# vlsibreakout.net
KiCad netlist of a schematic drawn in EAGLE
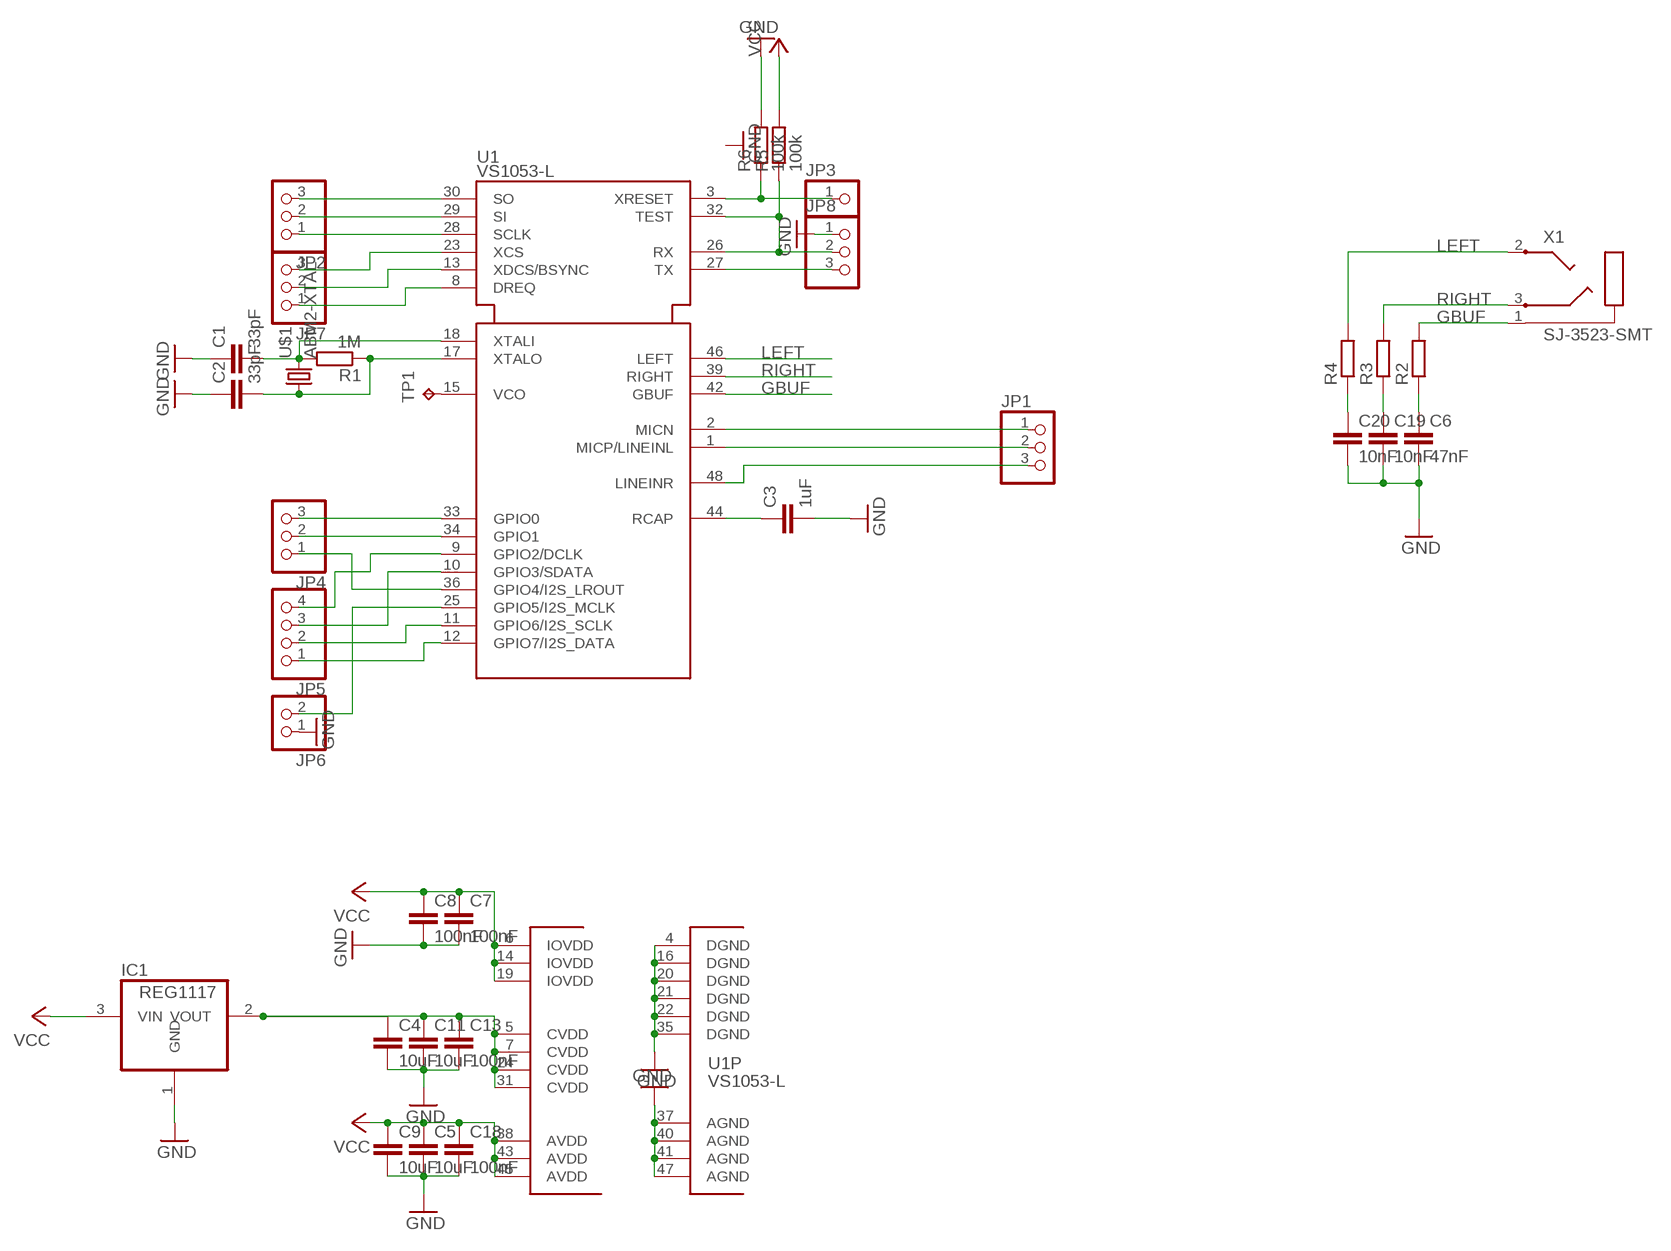
[diagram p0: schematic, sheet 1]

(export (version "E")
  (design (tool "Eeschema 10.0.6"))
  (components
    (comp (ref "C1")
      (value "33pF")
      (footprint "eagle-import:C0805")
      (libsource (lib "eagle-import") (part "C-EUC0805"))
    )
    (comp (ref "C2")
      (value "33pF")
      (footprint "eagle-import:C0805")
      (libsource (lib "eagle-import") (part "C-EUC0805"))
    )
    (comp (ref "C3")
      (value "1uF")
      (footprint "eagle-import:C0805")
      (libsource (lib "eagle-import") (part "C-EUC0805"))
    )
    (comp (ref "C4")
      (value "10uF")
      (footprint "eagle-import:C0805")
      (libsource (lib "eagle-import") (part "resistor_C-EUC0805"))
    )
    (comp (ref "C5")
      (value "10uF")
      (footprint "eagle-import:C0805")
      (libsource (lib "eagle-import") (part "resistor_C-EUC0805"))
    )
    (comp (ref "C6")
      (value "47nF")
      (footprint "eagle-import:C0603")
      (libsource (lib "eagle-import") (part "C-EUC0603"))
    )
    (comp (ref "C7")
      (value "100nF")
      (footprint "eagle-import:C0805")
      (libsource (lib "eagle-import") (part "resistor_C-EUC0805"))
    )
    (comp (ref "C8")
      (value "100nF")
      (footprint "eagle-import:C0805")
      (libsource (lib "eagle-import") (part "resistor_C-EUC0805"))
    )
    (comp (ref "C9")
      (value "10uF")
      (footprint "eagle-import:C0805")
      (libsource (lib "eagle-import") (part "resistor_C-EUC0805"))
    )
    (comp (ref "C11")
      (value "10uF")
      (footprint "eagle-import:C0805")
      (libsource (lib "eagle-import") (part "resistor_C-EUC0805"))
    )
    (comp (ref "C13")
      (value "100nF")
      (footprint "eagle-import:C0805")
      (libsource (lib "eagle-import") (part "resistor_C-EUC0805"))
    )
    (comp (ref "C18")
      (value "100nF")
      (footprint "eagle-import:C0805")
      (libsource (lib "eagle-import") (part "resistor_C-EUC0805"))
    )
    (comp (ref "C19")
      (value "10nF")
      (footprint "eagle-import:C0603")
      (libsource (lib "eagle-import") (part "C-EUC0603"))
    )
    (comp (ref "C20")
      (value "10nF")
      (footprint "eagle-import:C0603")
      (libsource (lib "eagle-import") (part "C-EUC0603"))
    )
    (comp (ref "IC1")
      (value "REG1117")
      (footprint "eagle-import:SOT223")
      (libsource (lib "eagle-import") (part "REG1117"))
    )
    (comp (ref "JP1")
      (value "PINHD-1X3")
      (footprint "eagle-import:1X03")
      (libsource (lib "eagle-import") (part "PINHD-1X3"))
    )
    (comp (ref "JP2")
      (value "PINHD-1X3")
      (footprint "eagle-import:1X03")
      (libsource (lib "eagle-import") (part "PINHD-1X3"))
    )
    (comp (ref "JP3")
      (value "PINHD-1X1")
      (footprint "eagle-import:1X01")
      (libsource (lib "eagle-import") (part "PINHD-1X1"))
    )
    (comp (ref "JP4")
      (value "PINHD-1X3")
      (footprint "eagle-import:1X03")
      (libsource (lib "eagle-import") (part "PINHD-1X3"))
    )
    (comp (ref "JP5")
      (value "PINHD-1X4")
      (footprint "eagle-import:1X04")
      (libsource (lib "eagle-import") (part "PINHD-1X4"))
    )
    (comp (ref "JP6")
      (value "PINHD-1X2")
      (footprint "eagle-import:1X02")
      (libsource (lib "eagle-import") (part "PINHD-1X2"))
    )
    (comp (ref "JP7")
      (value "PINHD-1X3")
      (footprint "eagle-import:1X03")
      (libsource (lib "eagle-import") (part "PINHD-1X3"))
    )
    (comp (ref "JP8")
      (value "PINHD-1X3")
      (footprint "eagle-import:1X03")
      (libsource (lib "eagle-import") (part "PINHD-1X3"))
    )
    (comp (ref "R1")
      (value "1M")
      (footprint "eagle-import:R0805")
      (libsource (lib "eagle-import") (part "R-EU_R0805"))
    )
    (comp (ref "R2")
      (value "R-EU_R0603")
      (footprint "eagle-import:R0603")
      (libsource (lib "eagle-import") (part "resistor_R-EU_R0603"))
    )
    (comp (ref "R3")
      (value "R-EU_R0603")
      (footprint "eagle-import:R0603")
      (libsource (lib "eagle-import") (part "resistor_R-EU_R0603"))
    )
    (comp (ref "R4")
      (value "R-EU_R0603")
      (footprint "eagle-import:R0603")
      (libsource (lib "eagle-import") (part "resistor_R-EU_R0603"))
    )
    (comp (ref "R5")
      (value "100k")
      (footprint "eagle-import:R0603")
      (libsource (lib "eagle-import") (part "R-EU_R0603"))
    )
    (comp (ref "R6")
      (value "100k")
      (footprint "eagle-import:R0603")
      (libsource (lib "eagle-import") (part "R-EU_R0603"))
    )
    (comp (ref "TP1")
      (value "TPB1,27")
      (footprint "eagle-import:B1,27")
      (libsource (lib "eagle-import") (part "TPB1,27"))
    )
    (comp (ref "U$1")
      (value "ABM2-XTAL")
      (footprint "eagle-import:ABM2")
      (libsource (lib "eagle-import") (part "ABM2-XTAL"))
    )
    (comp (ref "U1")
      (value "VS1053-L")
      (footprint "eagle-import:LQFP48")
      (libsource (lib "eagle-import") (part "VS1053-L"))
    )
    (comp (ref "X1")
      (value "SJ-3523-SMT")
      (footprint "eagle-import:SJ-3523-SMT")
      (libsource (lib "eagle-import") (part "SJ-3523-SMT"))
    )
  )
  (nets
    (net (code "1") (name "/GBUF") (class "Default")
      (node (ref "R2") (pin "2") (pinfunction "2_2") (pintype "passive"))
      (node (ref "U1") (pin "42") (pinfunction "GBUF_42") (pintype "output"))
      (node (ref "X1") (pin "1") (pinfunction "EARTH_1") (pintype "passive"))
    )
    (net (code "2") (name "/LEFT") (class "Default")
      (node (ref "R4") (pin "2") (pinfunction "2_2") (pintype "passive"))
      (node (ref "U1") (pin "46") (pinfunction "LEFT_46") (pintype "output"))
      (node (ref "X1") (pin "2") (pinfunction "TIP_2") (pintype "passive"))
    )
    (net (code "3") (name "/RIGHT") (class "Default")
      (node (ref "R3") (pin "2") (pinfunction "2_2") (pintype "passive"))
      (node (ref "U1") (pin "39") (pinfunction "RIGHT_39") (pintype "output"))
      (node (ref "X1") (pin "3") (pinfunction "RING_3") (pintype "passive"))
    )
    (net (code "4") (name "GND") (class "Default")
      (node (ref "C1") (pin "1") (pinfunction "1_1") (pintype "passive"))
      (node (ref "C11") (pin "2") (pinfunction "2_2") (pintype "passive"))
      (node (ref "C13") (pin "2") (pinfunction "2_2") (pintype "passive"))
      (node (ref "C18") (pin "2") (pinfunction "2_2") (pintype "passive"))
      (node (ref "C19") (pin "2") (pinfunction "2_2") (pintype "passive"))
      (node (ref "C2") (pin "1") (pinfunction "1_1") (pintype "passive"))
      (node (ref "C20") (pin "2") (pinfunction "2_2") (pintype "passive"))
      (node (ref "C3") (pin "2") (pinfunction "2_2") (pintype "passive"))
      (node (ref "C4") (pin "2") (pinfunction "2_2") (pintype "passive"))
      (node (ref "C5") (pin "2") (pinfunction "2_2") (pintype "passive"))
      (node (ref "C6") (pin "2") (pinfunction "2_2") (pintype "passive"))
      (node (ref "C7") (pin "2") (pinfunction "2_2") (pintype "passive"))
      (node (ref "C8") (pin "2") (pinfunction "2_2") (pintype "passive"))
      (node (ref "C9") (pin "2") (pinfunction "2_2") (pintype "passive"))
      (node (ref "IC1") (pin "1") (pinfunction "GND_1") (pintype "power_in"))
      (node (ref "JP6") (pin "1") (pinfunction "1_1") (pintype "passive"))
      (node (ref "JP8") (pin "1") (pinfunction "1_1") (pintype "passive"))
      (node (ref "R6") (pin "2") (pinfunction "2_2") (pintype "passive"))
      (node (ref "U1") (pin "16") (pinfunction "DGND_16") (pintype "power_in"))
      (node (ref "U1") (pin "20") (pinfunction "DGND_20") (pintype "power_in"))
      (node (ref "U1") (pin "21") (pinfunction "DGND_21") (pintype "power_in"))
      (node (ref "U1") (pin "22") (pinfunction "DGND_22") (pintype "power_in"))
      (node (ref "U1") (pin "35") (pinfunction "DGND_35") (pintype "power_in"))
      (node (ref "U1") (pin "37") (pinfunction "AGND_37") (pintype "power_in"))
      (node (ref "U1") (pin "4") (pinfunction "DGND_4") (pintype "power_in"))
      (node (ref "U1") (pin "40") (pinfunction "AGND_40") (pintype "power_in"))
      (node (ref "U1") (pin "41") (pinfunction "AGND_41") (pintype "power_in"))
      (node (ref "U1") (pin "47") (pinfunction "AGND_47") (pintype "power_in"))
    )
    (net (code "5") (name "Net-(C6-Pad1)") (class "Default")
      (node (ref "C6") (pin "1") (pinfunction "1_1") (pintype "passive"))
      (node (ref "R2") (pin "1") (pinfunction "1_1") (pintype "passive"))
    )
    (net (code "6") (name "Net-(C19-Pad1)") (class "Default")
      (node (ref "C19") (pin "1") (pinfunction "1_1") (pintype "passive"))
      (node (ref "R3") (pin "1") (pinfunction "1_1") (pintype "passive"))
    )
    (net (code "7") (name "Net-(C20-Pad1)") (class "Default")
      (node (ref "C20") (pin "1") (pinfunction "1_1") (pintype "passive"))
      (node (ref "R4") (pin "1") (pinfunction "1_1") (pintype "passive"))
    )
    (net (code "8") (name "Net-(IC1-VOUT)") (class "Default")
      (node (ref "C11") (pin "1") (pinfunction "1_1") (pintype "passive"))
      (node (ref "C13") (pin "1") (pinfunction "1_1") (pintype "passive"))
      (node (ref "C4") (pin "1") (pinfunction "1_1") (pintype "passive"))
      (node (ref "IC1") (pin "2") (pinfunction "VOUT_2") (pintype "output"))
      (node (ref "U1") (pin "24") (pinfunction "CVDD_24") (pintype "power_in"))
      (node (ref "U1") (pin "31") (pinfunction "CVDD_31") (pintype "power_in"))
      (node (ref "U1") (pin "5") (pinfunction "CVDD_5") (pintype "power_in"))
      (node (ref "U1") (pin "7") (pinfunction "CVDD_7") (pintype "power_in"))
    )
    (net (code "9") (name "Net-(U$1-1)") (class "Default")
      (node (ref "C2") (pin "2") (pinfunction "2_2") (pintype "passive"))
      (node (ref "R1") (pin "1") (pinfunction "1_1") (pintype "passive"))
      (node (ref "U$1") (pin "P$1") (pinfunction "1_P$1") (pintype "passive"))
      (node (ref "U1") (pin "17") (pinfunction "XTALO_17") (pintype "output"))
    )
    (net (code "10") (name "Net-(U$1-2)") (class "Default")
      (node (ref "C1") (pin "2") (pinfunction "2_2") (pintype "passive"))
      (node (ref "R1") (pin "2") (pinfunction "2_2") (pintype "passive"))
      (node (ref "U$1") (pin "P$2") (pinfunction "2_P$2") (pintype "passive"))
      (node (ref "U1") (pin "18") (pinfunction "XTALI_18") (pintype "input"))
    )
    (net (code "11") (name "Net-(U1A-DREQ)") (class "Default")
      (node (ref "JP7") (pin "1") (pinfunction "1_1") (pintype "passive"))
      (node (ref "U1") (pin "8") (pinfunction "DREQ_8") (pintype "output"))
    )
    (net (code "12") (name "Net-(U1A-GPIO0)") (class "Default")
      (node (ref "JP4") (pin "3") (pinfunction "3_3") (pintype "passive"))
      (node (ref "U1") (pin "33") (pinfunction "GPIO0_33") (pintype "bidirectional"))
    )
    (net (code "13") (name "Net-(U1A-GPIO1)") (class "Default")
      (node (ref "JP4") (pin "2") (pinfunction "2_2") (pintype "passive"))
      (node (ref "U1") (pin "34") (pinfunction "GPIO1_34") (pintype "bidirectional"))
    )
    (net (code "14") (name "Net-(U1A-GPIO2{slash}DCLK)") (class "Default")
      (node (ref "JP5") (pin "4") (pinfunction "4_4") (pintype "passive"))
      (node (ref "U1") (pin "9") (pinfunction "GPIO2/DCLK_9") (pintype "bidirectional"))
    )
    (net (code "15") (name "Net-(U1A-GPIO3{slash}SDATA)") (class "Default")
      (node (ref "JP5") (pin "3") (pinfunction "3_3") (pintype "passive"))
      (node (ref "U1") (pin "10") (pinfunction "GPIO3/SDATA_10") (pintype "bidirectional"))
    )
    (net (code "16") (name "Net-(U1A-GPIO4{slash}I2S_LROUT)") (class "Default")
      (node (ref "JP4") (pin "1") (pinfunction "1_1") (pintype "passive"))
      (node (ref "U1") (pin "36") (pinfunction "GPIO4/I2S_LROUT_36") (pintype "bidirectional"))
    )
    (net (code "17") (name "Net-(U1A-GPIO5{slash}I2S_MCLK)") (class "Default")
      (node (ref "JP6") (pin "2") (pinfunction "2_2") (pintype "passive"))
      (node (ref "U1") (pin "25") (pinfunction "GPIO5/I2S_MCLK_25") (pintype "bidirectional"))
    )
    (net (code "18") (name "Net-(U1A-GPIO6{slash}I2S_SCLK)") (class "Default")
      (node (ref "JP5") (pin "2") (pinfunction "2_2") (pintype "passive"))
      (node (ref "U1") (pin "11") (pinfunction "GPIO6/I2S_SCLK_11") (pintype "bidirectional"))
    )
    (net (code "19") (name "Net-(U1A-GPIO7{slash}I2S_DATA)") (class "Default")
      (node (ref "JP5") (pin "1") (pinfunction "1_1") (pintype "passive"))
      (node (ref "U1") (pin "12") (pinfunction "GPIO7/I2S_DATA_12") (pintype "bidirectional"))
    )
    (net (code "20") (name "Net-(U1A-LINEINR)") (class "Default")
      (node (ref "JP1") (pin "3") (pinfunction "3_3") (pintype "passive"))
      (node (ref "U1") (pin "48") (pinfunction "LINEINR_48") (pintype "input"))
    )
    (net (code "21") (name "Net-(U1A-MICN)") (class "Default")
      (node (ref "JP1") (pin "1") (pinfunction "1_1") (pintype "passive"))
      (node (ref "U1") (pin "2") (pinfunction "MICN_2") (pintype "input"))
    )
    (net (code "22") (name "Net-(U1A-MICP{slash}LINEINL)") (class "Default")
      (node (ref "JP1") (pin "2") (pinfunction "2_2") (pintype "passive"))
      (node (ref "U1") (pin "1") (pinfunction "MICP/LINEINL_1") (pintype "input"))
    )
    (net (code "23") (name "Net-(U1A-RCAP)") (class "Default")
      (node (ref "C3") (pin "1") (pinfunction "1_1") (pintype "passive"))
      (node (ref "U1") (pin "44") (pinfunction "RCAP_44") (pintype "bidirectional"))
    )
    (net (code "24") (name "Net-(U1A-RX)") (class "Default")
      (node (ref "JP8") (pin "2") (pinfunction "2_2") (pintype "passive"))
      (node (ref "R5") (pin "1") (pinfunction "1_1") (pintype "passive"))
      (node (ref "U1") (pin "26") (pinfunction "RX_26") (pintype "input"))
      (node (ref "U1") (pin "32") (pinfunction "TEST_32") (pintype "input"))
    )
    (net (code "25") (name "Net-(U1A-SCLK)") (class "Default")
      (node (ref "JP2") (pin "1") (pinfunction "1_1") (pintype "passive"))
      (node (ref "U1") (pin "28") (pinfunction "SCLK_28") (pintype "input"))
    )
    (net (code "26") (name "Net-(U1A-SI)") (class "Default")
      (node (ref "JP2") (pin "2") (pinfunction "2_2") (pintype "passive"))
      (node (ref "U1") (pin "29") (pinfunction "SI_29") (pintype "input"))
    )
    (net (code "27") (name "Net-(U1A-SO)") (class "Default")
      (node (ref "JP2") (pin "3") (pinfunction "3_3") (pintype "passive"))
      (node (ref "U1") (pin "30") (pinfunction "SO_30") (pintype "output"))
    )
    (net (code "28") (name "Net-(U1A-TX)") (class "Default")
      (node (ref "JP8") (pin "3") (pinfunction "3_3") (pintype "passive"))
      (node (ref "U1") (pin "27") (pinfunction "TX_27") (pintype "output"))
    )
    (net (code "29") (name "Net-(U1A-VCO)") (class "Default")
      (node (ref "TP1") (pin "TP") (pinfunction "TP_TP") (pintype "input"))
      (node (ref "U1") (pin "15") (pinfunction "VCO_15") (pintype "output"))
    )
    (net (code "30") (name "Net-(U1A-XCS)") (class "Default")
      (node (ref "JP7") (pin "3") (pinfunction "3_3") (pintype "passive"))
      (node (ref "U1") (pin "23") (pinfunction "XCS_23") (pintype "input"))
    )
    (net (code "31") (name "Net-(U1A-XDCS{slash}BSYNC)") (class "Default")
      (node (ref "JP7") (pin "2") (pinfunction "2_2") (pintype "passive"))
      (node (ref "U1") (pin "13") (pinfunction "XDCS/BSYNC_13") (pintype "input"))
    )
    (net (code "32") (name "Net-(U1A-XRESET)") (class "Default")
      (node (ref "JP3") (pin "1") (pinfunction "1_1") (pintype "passive"))
      (node (ref "R6") (pin "1") (pinfunction "1_1") (pintype "passive"))
      (node (ref "U1") (pin "3") (pinfunction "XRESET_3") (pintype "input"))
    )
    (net (code "33") (name "VCC") (class "Default")
      (node (ref "C18") (pin "1") (pinfunction "1_1") (pintype "passive"))
      (node (ref "C5") (pin "1") (pinfunction "1_1") (pintype "passive"))
      (node (ref "C7") (pin "1") (pinfunction "1_1") (pintype "passive"))
      (node (ref "C8") (pin "1") (pinfunction "1_1") (pintype "passive"))
      (node (ref "C9") (pin "1") (pinfunction "1_1") (pintype "passive"))
      (node (ref "IC1") (pin "3") (pinfunction "VIN_3") (pintype "input"))
      (node (ref "R5") (pin "2") (pinfunction "2_2") (pintype "passive"))
      (node (ref "U1") (pin "14") (pinfunction "IOVDD_14") (pintype "power_in"))
      (node (ref "U1") (pin "19") (pinfunction "IOVDD_19") (pintype "power_in"))
      (node (ref "U1") (pin "38") (pinfunction "AVDD_38") (pintype "power_in"))
      (node (ref "U1") (pin "43") (pinfunction "AVDD_43") (pintype "power_in"))
      (node (ref "U1") (pin "45") (pinfunction "AVDD_45") (pintype "power_in"))
      (node (ref "U1") (pin "6") (pinfunction "IOVDD_6") (pintype "power_in"))
    )
  )
)
